# AltiumDesigner_Schematic_1_2022-10-21.net
KiCad netlist of a schematic drawn in Altium Designer
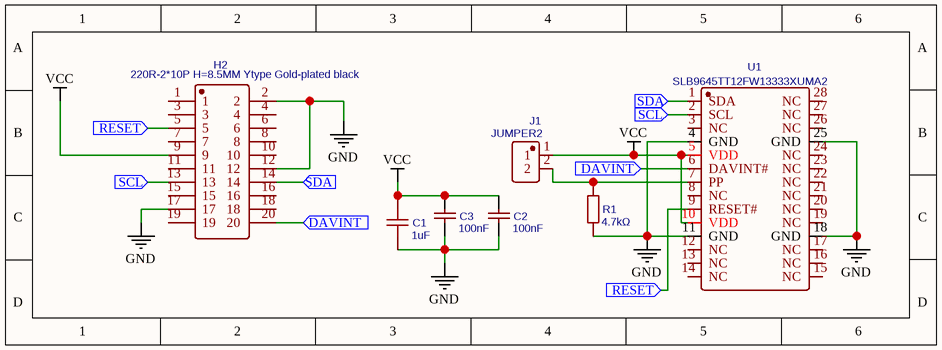
[diagram p0: AltiumDesigner_Schematic_1_2022-10-21.schdoc]

(export (version "E")
  (design (tool "Eeschema 10.0.6"))
  (components
    (comp (ref "C1")
      (value "1uF")
      (fields
        (field (name "BOM_MANUFACTURER PART") "CL31B105KBHNNNE")
        (field (name "BOM_SUPPLIER PART") "C1848")
      )
      (libsource (lib "altium-import") (part "root_1_1uF_"))
    )
    (comp (ref "C2")
      (value "100nF")
      (fields
        (field (name "BOM_MANUFACTURER PART") "CL31B104KBCNNNC")
        (field (name "BOM_SUPPLIER PART") "C24497")
      )
      (libsource (lib "altium-import") (part "root_1_100nF_"))
    )
    (comp (ref "C3")
      (value "100nF")
      (fields
        (field (name "BOM_MANUFACTURER PART") "CL31B104KBCNNNC")
        (field (name "BOM_SUPPLIER PART") "C24497")
      )
      (libsource (lib "altium-import") (part "root_1_100nF_"))
    )
    (comp (ref "H2")
      (value "220R-2*10P H=8.5MM Ytype Gold-plated black")
      (fields (field (name "BOM_SUPPLIER PART") "C124406") (field (name "CONTRIBUTOR") "LCSC"))
      (libsource (lib "altium-import") (part "root_0_220R-2*10P H=8.5MM Ytype Gold-plated black_"))
    )
    (comp (ref "J1")
      (value "JUMPER2")
      (fields
        (field (name "BOM_SUPPLIER PART") "C2940092")
        (field (name "BOM_MANUFACTURER PART") "Jumper2")
        (field (name "CONTRIBUTOR") "LCSC")
      )
      (libsource (lib "altium-import") (part "root_0_JUMPER2_"))
    )
    (comp (ref "R1")
      (value "4.7kΩ")
      (fields
        (field (name "BOM_SUPPLIER PART") "C269760")
        (field (name "BOM_MANUFACTURER PART") "RMC12064.7K5%N")
        (field (name "CONTRIBUTOR") "LCSC")
      )
      (libsource (lib "altium-import") (part "root_3_4.7kΩ_"))
    )
    (comp (ref "U1")
      (value "SLB9645TT12FW13333XUMA2")
      (fields (field (name "BOM_SUPPLIER PART") "C2651707") (field (name "CONTRIBUTOR") "lcsc"))
      (libsource (lib "altium-import") (part "root_0_SLB9645TT12FW13333XUMA2_"))
    )
  )
  (nets
    (net (code "1") (name "/DAVINT") (class "Default")
      (node (ref "H2") (pin "20") (pinfunction "20_20") (pintype "passive"))
      (node (ref "U1") (pin "6") (pinfunction "DAVINT#_6") (pintype "passive"))
    )
    (net (code "2") (name "/RESET") (class "Default")
      (node (ref "H2") (pin "5") (pinfunction "5_5") (pintype "passive"))
      (node (ref "U1") (pin "9") (pinfunction "RESET#_9") (pintype "passive"))
    )
    (net (code "3") (name "/SCL") (class "Default")
      (node (ref "H2") (pin "13") (pinfunction "13_13") (pintype "passive"))
      (node (ref "U1") (pin "2") (pinfunction "SCL_2") (pintype "passive"))
    )
    (net (code "4") (name "/SDA") (class "Default")
      (node (ref "H2") (pin "14") (pinfunction "14_14") (pintype "passive"))
      (node (ref "U1") (pin "1") (pinfunction "SDA_1") (pintype "passive"))
    )
    (net (code "5") (name "GND") (class "Default")
      (node (ref "C1") (pin "1") (pinfunction "1_1") (pintype "passive"))
      (node (ref "C2") (pin "1") (pinfunction "1_1") (pintype "passive"))
      (node (ref "C3") (pin "1") (pinfunction "1_1") (pintype "passive"))
      (node (ref "H2") (pin "12") (pinfunction "12_12") (pintype "passive"))
      (node (ref "H2") (pin "17") (pinfunction "17_17") (pintype "passive"))
      (node (ref "H2") (pin "2") (pinfunction "2_2") (pintype "passive"))
      (node (ref "R1") (pin "2") (pinfunction "2_2") (pintype "passive"))
      (node (ref "U1") (pin "11") (pinfunction "GND_11") (pintype "passive"))
      (node (ref "U1") (pin "18") (pinfunction "GND_18") (pintype "passive"))
      (node (ref "U1") (pin "25") (pinfunction "GND_25") (pintype "passive"))
      (node (ref "U1") (pin "4") (pinfunction "GND_4") (pintype "passive"))
    )
    (net (code "6") (name "Net-(U1-PP)") (class "Default")
      (node (ref "J1") (pin "2") (pinfunction "2_2") (pintype "passive"))
      (node (ref "R1") (pin "1") (pinfunction "1_1") (pintype "passive"))
      (node (ref "U1") (pin "7") (pinfunction "PP_7") (pintype "passive"))
    )
    (net (code "7") (name "VCC") (class "Default")
      (node (ref "C1") (pin "2") (pinfunction "2_2") (pintype "passive"))
      (node (ref "C2") (pin "2") (pinfunction "2_2") (pintype "passive"))
      (node (ref "C3") (pin "2") (pinfunction "2_2") (pintype "passive"))
      (node (ref "H2") (pin "9") (pinfunction "9_9") (pintype "passive"))
      (node (ref "J1") (pin "1") (pinfunction "1_1") (pintype "passive"))
      (node (ref "U1") (pin "10") (pinfunction "VDD_10") (pintype "passive"))
      (node (ref "U1") (pin "5") (pinfunction "VDD_5") (pintype "passive"))
    )
    (net (code "8") (name "unconnected-(H2-Pad1)") (class "Default")
      (node (ref "H2") (pin "1") (pinfunction "1_1") (pintype "passive"))
    )
    (net (code "9") (name "unconnected-(H2-Pad3)") (class "Default")
      (node (ref "H2") (pin "3") (pinfunction "3_3") (pintype "passive"))
    )
    (net (code "10") (name "unconnected-(H2-Pad4)") (class "Default")
      (node (ref "H2") (pin "4") (pinfunction "4_4") (pintype "passive"))
    )
    (net (code "11") (name "unconnected-(H2-Pad6)") (class "Default")
      (node (ref "H2") (pin "6") (pinfunction "6_6") (pintype "passive"))
    )
    (net (code "12") (name "unconnected-(H2-Pad7)") (class "Default")
      (node (ref "H2") (pin "7") (pinfunction "7_7") (pintype "passive"))
    )
    (net (code "13") (name "unconnected-(H2-Pad8)") (class "Default")
      (node (ref "H2") (pin "8") (pinfunction "8_8") (pintype "passive"))
    )
    (net (code "14") (name "unconnected-(H2-Pad10)") (class "Default")
      (node (ref "H2") (pin "10") (pinfunction "10_10") (pintype "passive"))
    )
    (net (code "15") (name "unconnected-(H2-Pad11)") (class "Default")
      (node (ref "H2") (pin "11") (pinfunction "11_11") (pintype "passive"))
    )
    (net (code "16") (name "unconnected-(H2-Pad15)") (class "Default")
      (node (ref "H2") (pin "15") (pinfunction "15_15") (pintype "passive"))
    )
    (net (code "17") (name "unconnected-(H2-Pad16)") (class "Default")
      (node (ref "H2") (pin "16") (pinfunction "16_16") (pintype "passive"))
    )
    (net (code "18") (name "unconnected-(H2-Pad18)") (class "Default")
      (node (ref "H2") (pin "18") (pinfunction "18_18") (pintype "passive"))
    )
    (net (code "19") (name "unconnected-(H2-Pad19)") (class "Default")
      (node (ref "H2") (pin "19") (pinfunction "19_19") (pintype "passive"))
    )
    (net (code "20") (name "unconnected-(U1-NC-Pad3)") (class "Default")
      (node (ref "U1") (pin "3") (pinfunction "NC_3") (pintype "passive"))
    )
    (net (code "21") (name "unconnected-(U1-NC-Pad8)") (class "Default")
      (node (ref "U1") (pin "8") (pinfunction "NC_8") (pintype "passive"))
    )
    (net (code "22") (name "unconnected-(U1-NC-Pad12)") (class "Default")
      (node (ref "U1") (pin "12") (pinfunction "NC_12") (pintype "passive"))
    )
    (net (code "23") (name "unconnected-(U1-NC-Pad13)") (class "Default")
      (node (ref "U1") (pin "13") (pinfunction "NC_13") (pintype "passive"))
    )
    (net (code "24") (name "unconnected-(U1-NC-Pad14)") (class "Default")
      (node (ref "U1") (pin "14") (pinfunction "NC_14") (pintype "passive"))
    )
    (net (code "25") (name "unconnected-(U1-NC-Pad15)") (class "Default")
      (node (ref "U1") (pin "15") (pinfunction "NC_15") (pintype "passive"))
    )
    (net (code "26") (name "unconnected-(U1-NC-Pad16)") (class "Default")
      (node (ref "U1") (pin "16") (pinfunction "NC_16") (pintype "passive"))
    )
    (net (code "27") (name "unconnected-(U1-NC-Pad17)") (class "Default")
      (node (ref "U1") (pin "17") (pinfunction "NC_17") (pintype "passive"))
    )
    (net (code "28") (name "unconnected-(U1-NC-Pad19)") (class "Default")
      (node (ref "U1") (pin "19") (pinfunction "NC_19") (pintype "passive"))
    )
    (net (code "29") (name "unconnected-(U1-NC-Pad20)") (class "Default")
      (node (ref "U1") (pin "20") (pinfunction "NC_20") (pintype "passive"))
    )
    (net (code "30") (name "unconnected-(U1-NC-Pad21)") (class "Default")
      (node (ref "U1") (pin "21") (pinfunction "NC_21") (pintype "passive"))
    )
    (net (code "31") (name "unconnected-(U1-NC-Pad22)") (class "Default")
      (node (ref "U1") (pin "22") (pinfunction "NC_22") (pintype "passive"))
    )
    (net (code "32") (name "unconnected-(U1-NC-Pad23)") (class "Default")
      (node (ref "U1") (pin "23") (pinfunction "NC_23") (pintype "passive"))
    )
    (net (code "33") (name "unconnected-(U1-NC-Pad24)") (class "Default")
      (node (ref "U1") (pin "24") (pinfunction "NC_24") (pintype "passive"))
    )
    (net (code "34") (name "unconnected-(U1-NC-Pad26)") (class "Default")
      (node (ref "U1") (pin "26") (pinfunction "NC_26") (pintype "passive"))
    )
    (net (code "35") (name "unconnected-(U1-NC-Pad27)") (class "Default")
      (node (ref "U1") (pin "27") (pinfunction "NC_27") (pintype "passive"))
    )
    (net (code "36") (name "unconnected-(U1-NC-Pad28)") (class "Default")
      (node (ref "U1") (pin "28") (pinfunction "NC_28") (pintype "passive"))
    )
  )
)
